# 05_-_Slow_Control.net
KiCad netlist of a schematic drawn in Altium Designer
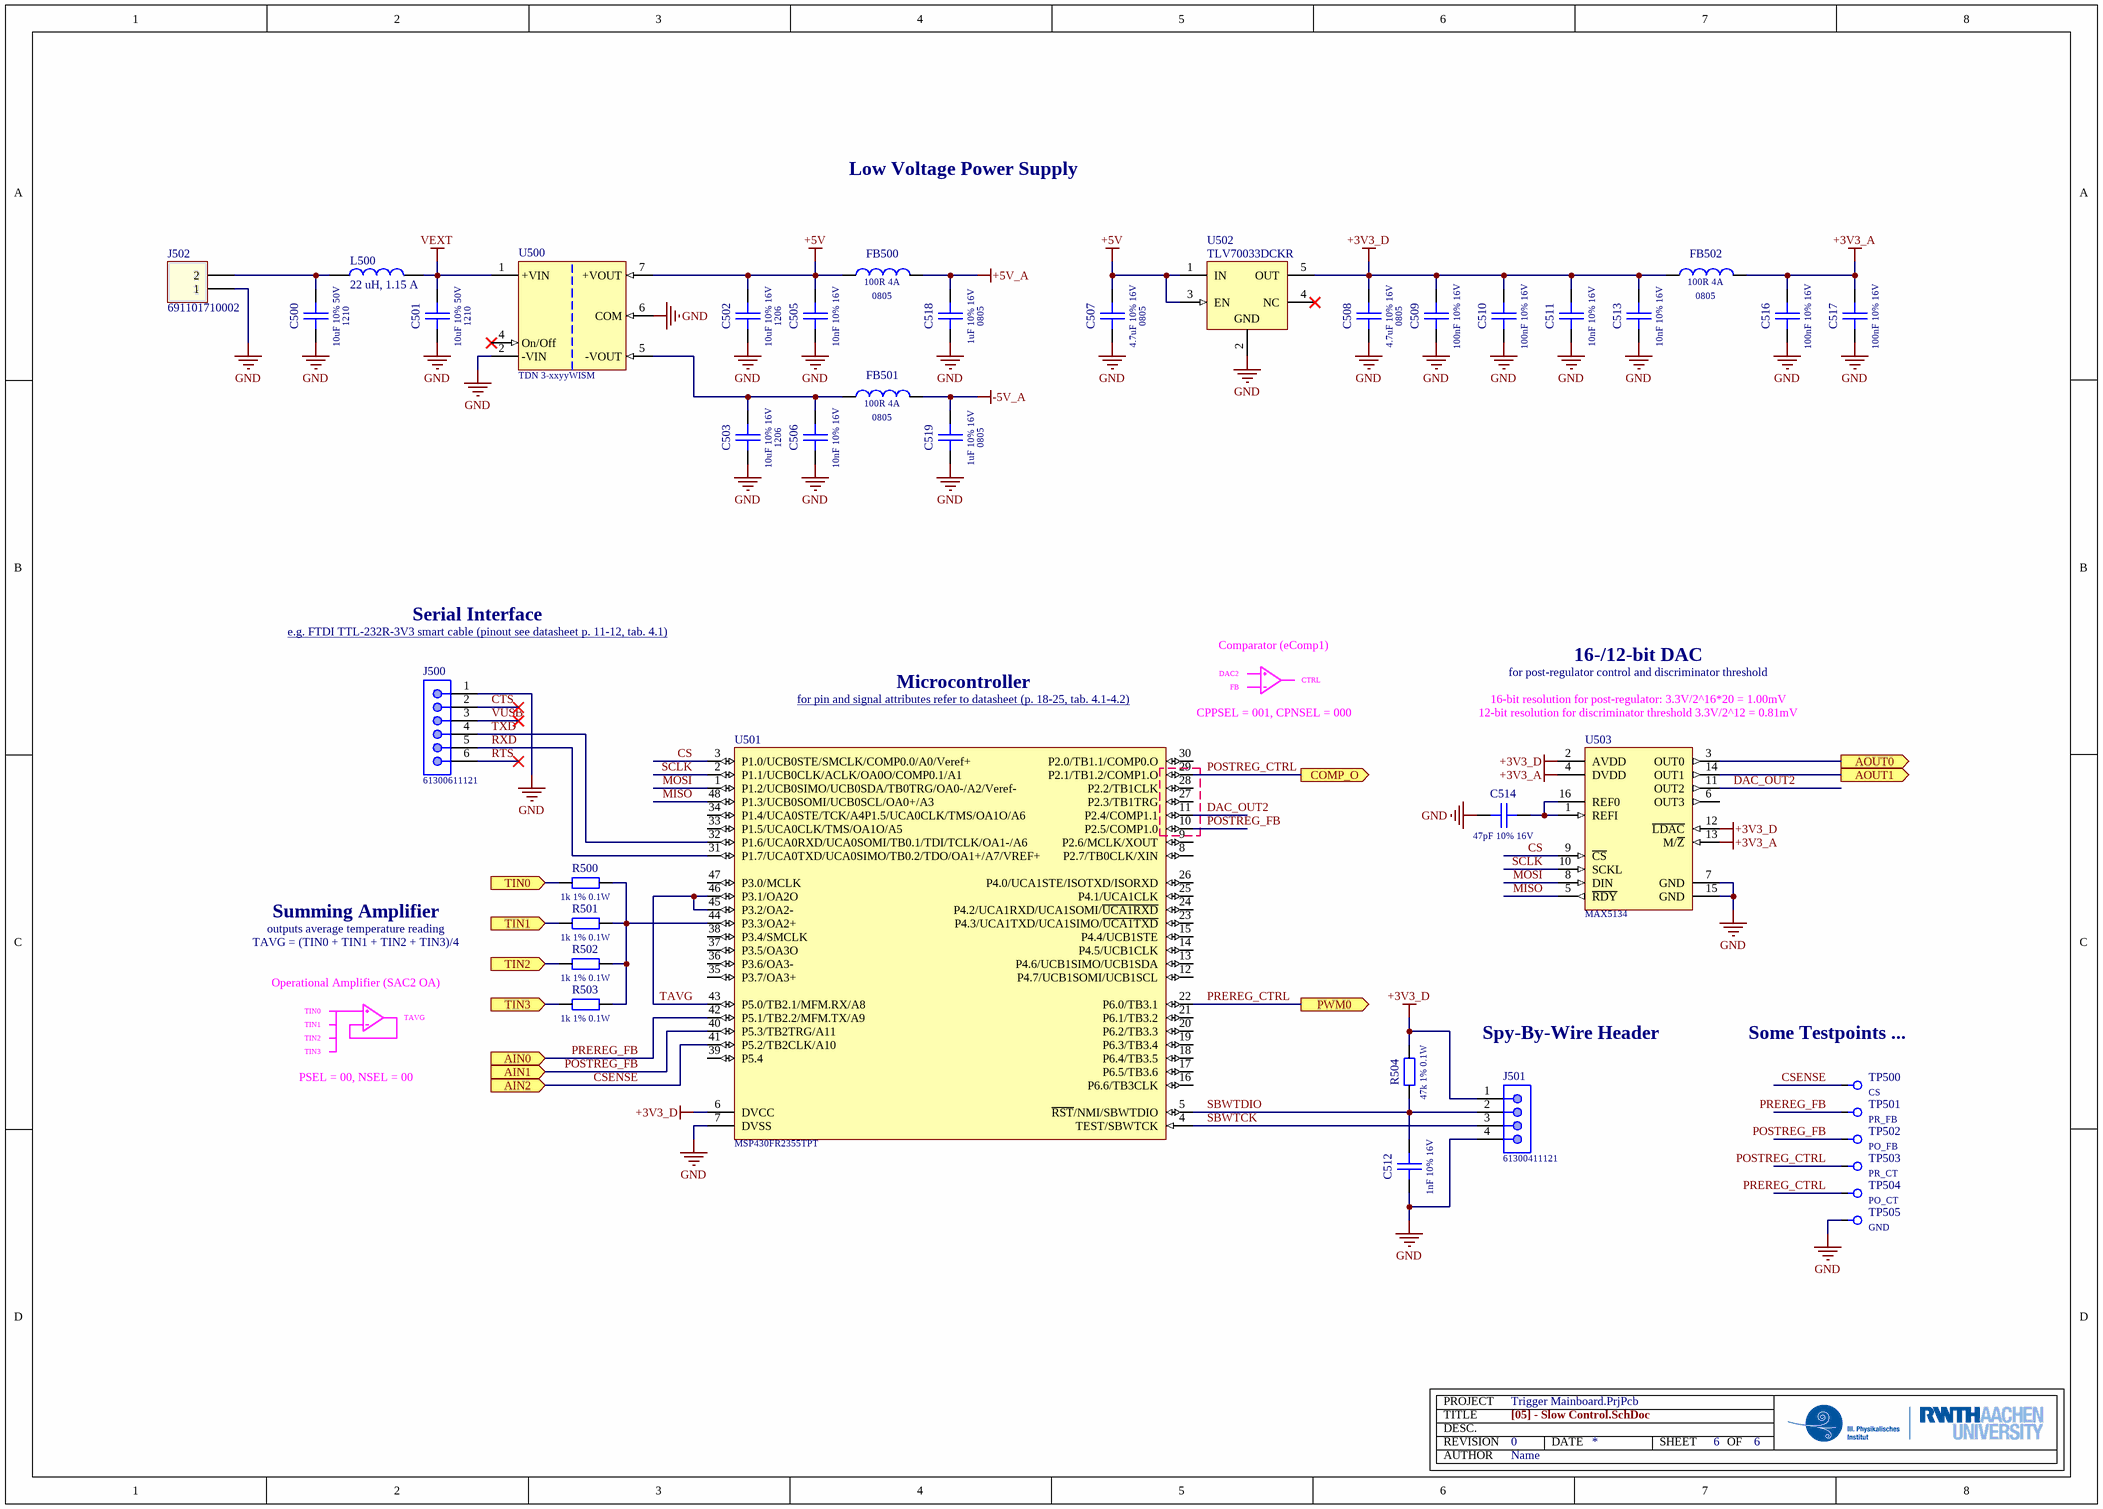
[diagram p0: [05] - Slow Control.SchDoc]

(export (version "E")
  (design (tool "Eeschema 10.0.6"))
  (components
    (comp (ref "C500")
      (value "10uF 10% 50V")
      (footprint "1210_CAP")
      (description "Simple generic capacitor.")
      (fields (field (name "PACKAGEREFERENCE") "1210"))
      (libsource (lib "CustomComponents") (part "Capacitor"))
    )
    (comp (ref "C501")
      (value "10uF 10% 50V")
      (footprint "1210_CAP")
      (description "Simple generic capacitor.")
      (fields (field (name "PACKAGEREFERENCE") "1210"))
      (libsource (lib "CustomComponents") (part "Capacitor"))
    )
    (comp (ref "C502")
      (value "10uF 10% 16V")
      (footprint "1206_CAP")
      (description "Simple generic capacitor.")
      (fields (field (name "PACKAGEREFERENCE") "1206"))
      (libsource (lib "CustomComponents") (part "Capacitor"))
    )
    (comp (ref "C503")
      (value "10uF 10% 16V")
      (footprint "1206_CAP")
      (description "Simple generic capacitor.")
      (fields (field (name "PACKAGEREFERENCE") "1206"))
      (libsource (lib "CustomComponents") (part "Capacitor"))
    )
    (comp (ref "C505")
      (value "10nF 10% 16V")
      (footprint "0603_CAP")
      (description "Simple generic capacitor.")
      (libsource (lib "CustomComponents") (part "Capacitor"))
    )
    (comp (ref "C506")
      (value "10nF 10% 16V")
      (footprint "0603_CAP")
      (description "Simple generic capacitor.")
      (libsource (lib "CustomComponents") (part "Capacitor"))
    )
    (comp (ref "C507")
      (value "4.7uF 10% 16V")
      (footprint "0805_CAP")
      (description "Simple generic capacitor.")
      (fields (field (name "PACKAGEREFERENCE") "0805"))
      (libsource (lib "CustomComponents") (part "Capacitor"))
    )
    (comp (ref "C508")
      (value "4.7uF 10% 16V")
      (footprint "0805_CAP")
      (description "Simple generic capacitor.")
      (fields (field (name "PACKAGEREFERENCE") "0805"))
      (libsource (lib "CustomComponents") (part "Capacitor"))
    )
    (comp (ref "C509")
      (value "100nF 10% 16V")
      (footprint "0603_CAP")
      (description "Simple generic capacitor.")
      (libsource (lib "CustomComponents") (part "Capacitor"))
    )
    (comp (ref "C510")
      (value "100nF 10% 16V")
      (footprint "0603_CAP")
      (description "Simple generic capacitor.")
      (libsource (lib "CustomComponents") (part "Capacitor"))
    )
    (comp (ref "C511")
      (value "10nF 10% 16V")
      (footprint "0603_CAP")
      (description "Simple generic capacitor.")
      (libsource (lib "CustomComponents") (part "Capacitor"))
    )
    (comp (ref "C512")
      (value "1nF 10% 16V")
      (footprint "0603_CAP")
      (description "Simple generic capacitor.")
      (libsource (lib "CustomComponents") (part "Capacitor"))
    )
    (comp (ref "C513")
      (value "10nF 10% 16V")
      (footprint "0603_CAP")
      (description "Simple generic capacitor.")
      (libsource (lib "CustomComponents") (part "Capacitor"))
    )
    (comp (ref "C514")
      (value "47pF 10% 16V")
      (footprint "0603_CAP")
      (description "Simple generic capacitor.")
      (libsource (lib "CustomComponents") (part "Capacitor"))
    )
    (comp (ref "C516")
      (value "100nF 10% 16V")
      (footprint "0603_CAP")
      (description "Simple generic capacitor.")
      (libsource (lib "CustomComponents") (part "Capacitor"))
    )
    (comp (ref "C517")
      (value "100nF 10% 16V")
      (footprint "0603_CAP")
      (description "Simple generic capacitor.")
      (libsource (lib "CustomComponents") (part "Capacitor"))
    )
    (comp (ref "C518")
      (value "1uF 10% 16V")
      (footprint "0805_CAP")
      (description "Simple generic capacitor.")
      (fields (field (name "PACKAGEREFERENCE") "0805"))
      (libsource (lib "CustomComponents") (part "Capacitor"))
    )
    (comp (ref "C519")
      (value "1uF 10% 16V")
      (footprint "0805_CAP")
      (description "Simple generic capacitor.")
      (fields (field (name "PACKAGEREFERENCE") "0805"))
      (libsource (lib "CustomComponents") (part "Capacitor"))
    )
    (comp (ref "FB500")
      (value "100R 4A")
      (footprint "0805_RES")
      (description "Simple generic inductor.")
      (fields
        (field (name "MANUFACTURER") "TDK")
        (field (name "PARTNUMBER") "MPZ2012S101ATD25")
        (field (name "PACKAGEREFERENCE") "0805")
      )
      (libsource (lib "CustomComponents") (part "Inductor"))
    )
    (comp (ref "FB501")
      (value "100R 4A")
      (footprint "0805_RES")
      (description "Simple generic inductor.")
      (fields
        (field (name "MANUFACTURER") "TDK")
        (field (name "PARTNUMBER") "MPZ2012S101ATD25")
        (field (name "PACKAGEREFERENCE") "0805")
      )
      (libsource (lib "CustomComponents") (part "Inductor"))
    )
    (comp (ref "FB502")
      (value "100R 4A")
      (footprint "0603_RES")
      (description "Simple generic inductor.")
      (fields
        (field (name "MANUFACTURER") "TDK")
        (field (name "PARTNUMBER") "MPZ2012S101ATD25")
        (field (name "PACKAGEREFERENCE") "0805")
      )
      (libsource (lib "CustomComponents") (part "Inductor"))
    )
    (comp (ref "J500")
      (value "61300611121")
      (footprint "61300611121")
      (description "WR-PHD Pin Header, THT, pitch 2.54mm, Single Row, Vertical, 6pin")
      (fields (field (name "PUBLISHER") "Wurth Elektronik"))
      (libsource (lib "WR-PHD") (part "61300611121"))
    )
    (comp (ref "J501")
      (value "61300411121")
      (footprint "61300411121")
      (description "WR-PHD Pin Header, THT, pitch 2.54mm, Single Row, Vertical, 4pin")
      (fields (field (name "PUBLISHER") "Wurth Elektronik"))
      (libsource (lib "WR-PHD") (part "61300411121"))
    )
    (comp (ref "J502")
      (value "691101710002")
      (footprint "691101710002")
      (description "WR-TBL Serie 101 - 5.00 mm Horizontal Entry Modular, 02p")
      (fields (field (name "PUBLISHER") "Wurth Elektronik"))
      (libsource (lib "WE-5.00mm Header") (part "691101710002"))
    )
    (comp (ref "L500")
      (value "22 uH, 1.15 A")
      (footprint "WE-TPC_5828")
      (description "SMT Shielded Tiny Power Inductor WE-TPC, size 5828, 22 uH, 1.15 A")
      (fields (field (name "PART NUMBER") "744053220") (field (name "PUBLISHER") "Wurth Elektronik"))
      (libsource (lib "altium-import") (part "root_0_744053220_"))
    )
    (comp (ref "R500")
      (value "1k 1% 0.1W")
      (footprint "0603_RES")
      (description "Simple generic resistor.")
      (libsource (lib "CustomComponents") (part "Resistor"))
    )
    (comp (ref "R501")
      (value "1k 1% 0.1W")
      (footprint "0603_RES")
      (description "Simple generic resistor.")
      (libsource (lib "CustomComponents") (part "Resistor"))
    )
    (comp (ref "R502")
      (value "1k 1% 0.1W")
      (footprint "0603_RES")
      (description "Simple generic resistor.")
      (libsource (lib "CustomComponents") (part "Resistor"))
    )
    (comp (ref "R503")
      (value "1k 1% 0.1W")
      (footprint "0603_RES")
      (description "Simple generic resistor.")
      (libsource (lib "CustomComponents") (part "Resistor"))
    )
    (comp (ref "R504")
      (value "47k 1% 0.1W")
      (footprint "0603_RES")
      (description "Simple generic resistor.")
      (libsource (lib "CustomComponents") (part "Resistor"))
    )
    (comp (ref "TP500")
      (value "CS")
      (footprint "TESTPOINT_5019")
      (fields (field (name "MANUFACTURER") "Keystone Electronics") (field (name "PARTNUMBER") "500X"))
      (libsource (lib "CustomComponents") (part "Testpoint"))
    )
    (comp (ref "TP501")
      (value "PR_FB")
      (footprint "TESTPOINT_5019")
      (fields (field (name "MANUFACTURER") "Keystone Electronics") (field (name "PARTNUMBER") "500X"))
      (libsource (lib "CustomComponents") (part "Testpoint"))
    )
    (comp (ref "TP502")
      (value "PO_FB")
      (footprint "TESTPOINT_5019")
      (fields (field (name "MANUFACTURER") "Keystone Electronics") (field (name "PARTNUMBER") "500X"))
      (libsource (lib "CustomComponents") (part "Testpoint"))
    )
    (comp (ref "TP503")
      (value "PR_CT")
      (footprint "TESTPOINT_5019")
      (fields (field (name "MANUFACTURER") "Keystone Electronics") (field (name "PARTNUMBER") "500X"))
      (libsource (lib "CustomComponents") (part "Testpoint"))
    )
    (comp (ref "TP504")
      (value "PO_CT")
      (footprint "TESTPOINT_5019")
      (fields (field (name "MANUFACTURER") "Keystone Electronics") (field (name "PARTNUMBER") "500X"))
      (libsource (lib "CustomComponents") (part "Testpoint"))
    )
    (comp (ref "TP505")
      (value "GND")
      (footprint "TESTPOINT_5019")
      (fields (field (name "MANUFACTURER") "Keystone Electronics") (field (name "PARTNUMBER") "500X"))
      (libsource (lib "CustomComponents") (part "Testpoint"))
    )
    (comp (ref "U500")
      (value "TDN 3-xxyyWISM")
      (footprint "TDN_3WISM-PACK")
      (description "TDN 3WISM Series, 3 Watt DC/DC converter.")
      (fields (field (name "MANUFACTURER") "Traco Power"))
      (libsource (lib "CustomComponents") (part "_BLANK_1"))
    )
    (comp (ref "U501")
      (value "MSP430FR2355TPT")
      (footprint "PQFP-48")
      (description "Mixed-Signal Microcontroller.")
      (fields (field (name "MANUFACTURER") "Texas Instruments"))
      (libsource (lib "CustomComponents") (part "MSP430FR2355TPT"))
    )
    (comp (ref "U502")
      (value "TLV70033DCKR")
      (footprint "TI-DCK5_V")
      (fields (field (name "MANUFACTURER") "Texas Instruments"))
      (libsource (lib "TI Power Management Linear Regulator Single Channel LDO (0-350mA)") (part "TLV70033DCKR"))
    )
    (comp (ref "U503")
      (value "MAX5134")
      (footprint "TSSOP-16")
      (description "Pin-/Software-Compatible, 16-/12-Bit, Voltage-Output DACs.")
      (fields (field (name "MANUFACTURER") "Maxim Integrated") (field (name "PARTNUMBER") "MAX5134AGUE+"))
      (libsource (lib "CustomComponents") (part "MAX5134"))
    )
  )
  (nets
    (net (code "1") (name "+3V3_A") (class "Default")
      (node (ref "C516") (pin "2") (pinfunction "2_2") (pintype "passive"))
      (node (ref "C517") (pin "2") (pinfunction "2_2") (pintype "passive"))
      (node (ref "FB502") (pin "2") (pinfunction "2_2") (pintype "passive"))
      (node (ref "U503") (pin "13") (pinfunction "M/~{Z}_13") (pintype "input"))
      (node (ref "U503") (pin "4") (pinfunction "DVDD_4") (pintype "power_in"))
    )
    (net (code "2") (name "+3V3_D") (class "Default")
      (node (ref "C508") (pin "2") (pinfunction "2_2") (pintype "passive"))
      (node (ref "C509") (pin "2") (pinfunction "2_2") (pintype "passive"))
      (node (ref "C510") (pin "2") (pinfunction "2_2") (pintype "passive"))
      (node (ref "C511") (pin "2") (pinfunction "2_2") (pintype "passive"))
      (node (ref "C513") (pin "2") (pinfunction "2_2") (pintype "passive"))
      (node (ref "FB502") (pin "1") (pinfunction "1_1") (pintype "passive"))
      (node (ref "J501") (pin "1") (pinfunction "1_1") (pintype "passive"))
      (node (ref "R504") (pin "1") (pinfunction "1_1") (pintype "passive"))
      (node (ref "U501") (pin "6") (pinfunction "DVCC_6") (pintype "passive"))
      (node (ref "U502") (pin "5") (pinfunction "OUT_5") (pintype "power_in"))
      (node (ref "U503") (pin "12") (pinfunction "~{LDAC}_12") (pintype "input"))
      (node (ref "U503") (pin "2") (pinfunction "AVDD_2") (pintype "power_in"))
    )
    (net (code "3") (name "+5V") (class "Default")
      (node (ref "C502") (pin "2") (pinfunction "2_2") (pintype "passive"))
      (node (ref "C505") (pin "2") (pinfunction "2_2") (pintype "passive"))
      (node (ref "C507") (pin "2") (pinfunction "2_2") (pintype "passive"))
      (node (ref "FB500") (pin "1") (pinfunction "1_1") (pintype "passive"))
      (node (ref "U500") (pin "7") (pinfunction "+VOUT_7") (pintype "input"))
      (node (ref "U502") (pin "1") (pinfunction "IN_1") (pintype "power_in"))
      (node (ref "U502") (pin "3") (pinfunction "EN_3") (pintype "input"))
    )
    (net (code "4") (name "+5V_A") (class "Default")
      (node (ref "C518") (pin "2") (pinfunction "2_2") (pintype "passive"))
      (node (ref "FB500") (pin "2") (pinfunction "2_2") (pintype "passive"))
    )
    (net (code "5") (name "-5V_A") (class "Default")
      (node (ref "C519") (pin "2") (pinfunction "2_2") (pintype "passive"))
      (node (ref "FB501") (pin "2") (pinfunction "2_2") (pintype "passive"))
    )
    (net (code "6") (name "/AOUT0") (class "Default")
      (node (ref "U503") (pin "3") (pinfunction "OUT0_3") (pintype "output"))
    )
    (net (code "7") (name "/AOUT1") (class "Default")
      (node (ref "U503") (pin "14") (pinfunction "OUT1_14") (pintype "output"))
    )
    (net (code "8") (name "/CS") (class "Default")
      (node (ref "U501") (pin "3") (pinfunction "P1.0/UCB0STE/SMCLK/COMP0.0/A0/Veref+_3") (pintype "bidirectional"))
      (node (ref "U503") (pin "9") (pinfunction "~{CS}_9") (pintype "input"))
    )
    (net (code "9") (name "/CSENSE") (class "Default")
      (node (ref "TP500") (pin "1") (pinfunction "1_1") (pintype "passive"))
      (node (ref "U501") (pin "41") (pinfunction "P5.2/TB2CLK/A10_41") (pintype "bidirectional"))
    )
    (net (code "10") (name "/DAC_OUT2") (class "Default")
      (node (ref "U501") (pin "11") (pinfunction "P2.4/COMP1.1_11") (pintype "bidirectional"))
      (node (ref "U503") (pin "11") (pinfunction "OUT2_11") (pintype "output"))
    )
    (net (code "11") (name "/MISO") (class "Default")
      (node (ref "U501") (pin "48") (pinfunction "P1.3/UCB0SOMI/UCB0SCL/OA0+/A3_48") (pintype "bidirectional"))
      (node (ref "U503") (pin "5") (pinfunction "~{RDY}_5") (pintype "output"))
    )
    (net (code "12") (name "/MOSI") (class "Default")
      (node (ref "U501") (pin "1") (pinfunction "P1.2/UCB0SIMO/UCB0SDA/TB0TRG/OA0-/A2/Veref-_1") (pintype "bidirectional"))
      (node (ref "U503") (pin "8") (pinfunction "DIN_8") (pintype "input"))
    )
    (net (code "13") (name "/POSTREG_CTRL") (class "Default")
      (node (ref "TP503") (pin "1") (pinfunction "1_1") (pintype "passive"))
      (node (ref "U501") (pin "29") (pinfunction "P2.1/TB1.2/COMP1.O_29") (pintype "bidirectional"))
    )
    (net (code "14") (name "/POSTREG_FB") (class "Default")
      (node (ref "TP502") (pin "1") (pinfunction "1_1") (pintype "passive"))
      (node (ref "U501") (pin "10") (pinfunction "P2.5/COMP1.0_10") (pintype "bidirectional"))
      (node (ref "U501") (pin "40") (pinfunction "P5.3/TB2TRG/A11_40") (pintype "bidirectional"))
    )
    (net (code "15") (name "/PREREG_CTRL") (class "Default")
      (node (ref "TP504") (pin "1") (pinfunction "1_1") (pintype "passive"))
      (node (ref "U501") (pin "22") (pinfunction "P6.0/TB3.1_22") (pintype "bidirectional"))
    )
    (net (code "16") (name "/PREREG_FB") (class "Default")
      (node (ref "TP501") (pin "1") (pinfunction "1_1") (pintype "passive"))
      (node (ref "U501") (pin "42") (pinfunction "P5.1/TB2.2/MFM.TX/A9_42") (pintype "bidirectional"))
    )
    (net (code "17") (name "/RXD") (class "Default")
      (node (ref "J500") (pin "5") (pinfunction "5_5") (pintype "passive"))
      (node (ref "U501") (pin "31") (pinfunction "P1.7/UCA0TXD/UCA0SIMO/TB0.2/TDO/OA1+/A7/VREF+_31") (pintype "bidirectional"))
    )
    (net (code "18") (name "/SBWTCK") (class "Default")
      (node (ref "J501") (pin "3") (pinfunction "3_3") (pintype "passive"))
      (node (ref "U501") (pin "4") (pinfunction "TEST/SBWTCK_4") (pintype "input"))
    )
    (net (code "19") (name "/SBWTDIO") (class "Default")
      (node (ref "C512") (pin "2") (pinfunction "2_2") (pintype "passive"))
      (node (ref "J501") (pin "2") (pinfunction "2_2") (pintype "passive"))
      (node (ref "R504") (pin "2") (pinfunction "2_2") (pintype "passive"))
      (node (ref "U501") (pin "5") (pinfunction "~{RST}/NMI/SBWTDIO_5") (pintype "bidirectional"))
    )
    (net (code "20") (name "/SCLK") (class "Default")
      (node (ref "U501") (pin "2") (pinfunction "P1.1/UCB0CLK/ACLK/OA0O/COMP0.1/A1_2") (pintype "bidirectional"))
      (node (ref "U503") (pin "10") (pinfunction "SCKL_10") (pintype "input"))
    )
    (net (code "21") (name "/TAVG") (class "Default")
      (node (ref "U501") (pin "43") (pinfunction "P5.0/TB2.1/MFM.RX/A8_43") (pintype "bidirectional"))
      (node (ref "U501") (pin "45") (pinfunction "P3.2/OA2-_45") (pintype "bidirectional"))
      (node (ref "U501") (pin "46") (pinfunction "P3.1/OA2O_46") (pintype "bidirectional"))
    )
    (net (code "22") (name "/TIN0") (class "Default")
      (node (ref "R500") (pin "2") (pinfunction "2_2") (pintype "passive"))
    )
    (net (code "23") (name "/TIN1") (class "Default")
      (node (ref "R501") (pin "2") (pinfunction "2_2") (pintype "passive"))
    )
    (net (code "24") (name "/TIN2") (class "Default")
      (node (ref "R502") (pin "2") (pinfunction "2_2") (pintype "passive"))
    )
    (net (code "25") (name "/TIN3") (class "Default")
      (node (ref "R503") (pin "2") (pinfunction "2_2") (pintype "passive"))
    )
    (net (code "26") (name "/TXD") (class "Default")
      (node (ref "J500") (pin "4") (pinfunction "4_4") (pintype "passive"))
      (node (ref "U501") (pin "32") (pinfunction "P1.6/UCA0RXD/UCA0SOMI/TB0.1/TDI/TCLK/OA1-/A6_32") (pintype "bidirectional"))
    )
    (net (code "27") (name "/VUSB") (class "Default")
      (node (ref "J500") (pin "3") (pinfunction "3_3") (pintype "passive+no_connect"))
    )
    (net (code "28") (name "/~{CTS}") (class "Default")
      (node (ref "J500") (pin "2") (pinfunction "2_2") (pintype "passive+no_connect"))
    )
    (net (code "29") (name "/~{RTS}") (class "Default")
      (node (ref "J500") (pin "6") (pinfunction "6_6") (pintype "passive+no_connect"))
    )
    (net (code "30") (name "GND") (class "Default")
      (node (ref "C500") (pin "1") (pinfunction "1_1") (pintype "passive"))
      (node (ref "C501") (pin "1") (pinfunction "1_1") (pintype "passive"))
      (node (ref "C502") (pin "1") (pinfunction "1_1") (pintype "passive"))
      (node (ref "C503") (pin "1") (pinfunction "1_1") (pintype "passive"))
      (node (ref "C505") (pin "1") (pinfunction "1_1") (pintype "passive"))
      (node (ref "C506") (pin "1") (pinfunction "1_1") (pintype "passive"))
      (node (ref "C507") (pin "1") (pinfunction "1_1") (pintype "passive"))
      (node (ref "C508") (pin "1") (pinfunction "1_1") (pintype "passive"))
      (node (ref "C509") (pin "1") (pinfunction "1_1") (pintype "passive"))
      (node (ref "C510") (pin "1") (pinfunction "1_1") (pintype "passive"))
      (node (ref "C511") (pin "1") (pinfunction "1_1") (pintype "passive"))
      (node (ref "C512") (pin "1") (pinfunction "1_1") (pintype "passive"))
      (node (ref "C513") (pin "1") (pinfunction "1_1") (pintype "passive"))
      (node (ref "C514") (pin "1") (pinfunction "1_1") (pintype "passive"))
      (node (ref "C516") (pin "1") (pinfunction "1_1") (pintype "passive"))
      (node (ref "C517") (pin "1") (pinfunction "1_1") (pintype "passive"))
      (node (ref "C518") (pin "1") (pinfunction "1_1") (pintype "passive"))
      (node (ref "C519") (pin "1") (pinfunction "1_1") (pintype "passive"))
      (node (ref "J500") (pin "1") (pinfunction "1_1") (pintype "passive"))
      (node (ref "J501") (pin "4") (pinfunction "4_4") (pintype "passive"))
      (node (ref "J502") (pin "1") (pinfunction "1_1") (pintype "passive"))
      (node (ref "TP505") (pin "1") (pinfunction "1_1") (pintype "passive"))
      (node (ref "U500") (pin "2") (pinfunction "-VIN_2") (pintype "power_in"))
      (node (ref "U500") (pin "6") (pinfunction "COM_6") (pintype "input"))
      (node (ref "U501") (pin "7") (pinfunction "DVSS_7") (pintype "passive"))
      (node (ref "U502") (pin "2") (pinfunction "GND_2") (pintype "power_in"))
      (node (ref "U503") (pin "15") (pinfunction "GND_15") (pintype "power_in"))
      (node (ref "U503") (pin "7") (pinfunction "GND_7") (pintype "power_in"))
    )
    (net (code "31") (name "Net-(C500-Pad2)") (class "Default")
      (node (ref "C500") (pin "2") (pinfunction "2_2") (pintype "passive"))
      (node (ref "J502") (pin "2") (pinfunction "2_2") (pintype "passive"))
      (node (ref "L500") (pin "1") (pinfunction "1_1") (pintype "passive"))
    )
    (net (code "32") (name "Net-(U500--VOUT)") (class "Default")
      (node (ref "C503") (pin "2") (pinfunction "2_2") (pintype "passive"))
      (node (ref "C506") (pin "2") (pinfunction "2_2") (pintype "passive"))
      (node (ref "FB501") (pin "1") (pinfunction "1_1") (pintype "passive"))
      (node (ref "U500") (pin "5") (pinfunction "-VOUT_5") (pintype "input"))
    )
    (net (code "33") (name "Net-(U501-P3.3{slash}OA2+)") (class "Default")
      (node (ref "R500") (pin "1") (pinfunction "1_1") (pintype "passive"))
      (node (ref "R501") (pin "1") (pinfunction "1_1") (pintype "passive"))
      (node (ref "R502") (pin "1") (pinfunction "1_1") (pintype "passive"))
      (node (ref "R503") (pin "1") (pinfunction "1_1") (pintype "passive"))
      (node (ref "U501") (pin "44") (pinfunction "P3.3/OA2+_44") (pintype "bidirectional"))
    )
    (net (code "34") (name "Net-(U503-REF0)") (class "Default")
      (node (ref "C514") (pin "2") (pinfunction "2_2") (pintype "passive"))
      (node (ref "U503") (pin "1") (pinfunction "REFI_1") (pintype "input"))
      (node (ref "U503") (pin "16") (pinfunction "REF0_16") (pintype "power_in"))
    )
    (net (code "35") (name "VEXT") (class "Default")
      (node (ref "C501") (pin "2") (pinfunction "2_2") (pintype "passive"))
      (node (ref "L500") (pin "2") (pinfunction "2_2") (pintype "passive"))
      (node (ref "U500") (pin "1") (pinfunction "+VIN_1") (pintype "power_in"))
    )
    (net (code "36") (name "unconnected-(U500-On{slash}Off-Pad4)") (class "Default")
      (node (ref "U500") (pin "4") (pinfunction "On/Off_4") (pintype "input+no_connect"))
    )
    (net (code "37") (name "unconnected-(U501-P1.4{slash}UCA0STE{slash}TCK{slash}A4P1.5{slash}UCA0CLK{slash}TMS{slash}OA1O{slash}A6-Pad34)") (class "Default")
      (node (ref "U501") (pin "34") (pinfunction "P1.4/UCA0STE/TCK/A4P1.5/UCA0CLK/TMS/OA1O/A6_34") (pintype "bidirectional"))
    )
    (net (code "38") (name "unconnected-(U501-P1.5{slash}UCA0CLK{slash}TMS{slash}OA1O{slash}A5-Pad33)") (class "Default")
      (node (ref "U501") (pin "33") (pinfunction "P1.5/UCA0CLK/TMS/OA1O/A5_33") (pintype "bidirectional"))
    )
    (net (code "39") (name "unconnected-(U501-P2.0{slash}TB1.1{slash}COMP0.O-Pad30)") (class "Default")
      (node (ref "U501") (pin "30") (pinfunction "P2.0/TB1.1/COMP0.O_30") (pintype "bidirectional"))
    )
    (net (code "40") (name "unconnected-(U501-P2.2{slash}TB1CLK-Pad28)") (class "Default")
      (node (ref "U501") (pin "28") (pinfunction "P2.2/TB1CLK_28") (pintype "bidirectional"))
    )
    (net (code "41") (name "unconnected-(U501-P2.3{slash}TB1TRG-Pad27)") (class "Default")
      (node (ref "U501") (pin "27") (pinfunction "P2.3/TB1TRG_27") (pintype "bidirectional"))
    )
    (net (code "42") (name "unconnected-(U501-P2.6{slash}MCLK{slash}XOUT-Pad9)") (class "Default")
      (node (ref "U501") (pin "9") (pinfunction "P2.6/MCLK/XOUT_9") (pintype "bidirectional"))
    )
    (net (code "43") (name "unconnected-(U501-P2.7{slash}TB0CLK{slash}XIN-Pad8)") (class "Default")
      (node (ref "U501") (pin "8") (pinfunction "P2.7/TB0CLK/XIN_8") (pintype "bidirectional"))
    )
    (net (code "44") (name "unconnected-(U501-P3.0{slash}MCLK-Pad47)") (class "Default")
      (node (ref "U501") (pin "47") (pinfunction "P3.0/MCLK_47") (pintype "bidirectional"))
    )
    (net (code "45") (name "unconnected-(U501-P3.4{slash}SMCLK-Pad38)") (class "Default")
      (node (ref "U501") (pin "38") (pinfunction "P3.4/SMCLK_38") (pintype "bidirectional"))
    )
    (net (code "46") (name "unconnected-(U501-P3.5{slash}OA3O-Pad37)") (class "Default")
      (node (ref "U501") (pin "37") (pinfunction "P3.5/OA3O_37") (pintype "bidirectional"))
    )
    (net (code "47") (name "unconnected-(U501-P3.6{slash}OA3--Pad36)") (class "Default")
      (node (ref "U501") (pin "36") (pinfunction "P3.6/OA3-_36") (pintype "bidirectional"))
    )
    (net (code "48") (name "unconnected-(U501-P3.7{slash}OA3+-Pad35)") (class "Default")
      (node (ref "U501") (pin "35") (pinfunction "P3.7/OA3+_35") (pintype "bidirectional"))
    )
    (net (code "49") (name "unconnected-(U501-P4.0{slash}UCA1STE{slash}ISOTXD{slash}ISORXD-Pad26)") (class "Default")
      (node (ref "U501") (pin "26") (pinfunction "P4.0/UCA1STE/ISOTXD/ISORXD_26") (pintype "bidirectional"))
    )
    (net (code "50") (name "unconnected-(U501-P4.1{slash}UCA1CLK-Pad25)") (class "Default")
      (node (ref "U501") (pin "25") (pinfunction "P4.1/UCA1CLK_25") (pintype "bidirectional"))
    )
    (net (code "51") (name "unconnected-(U501-P4.2{slash}UCA1RXD{slash}UCA1SOMI{slash}~{UCA1RXD}-Pad24)") (class "Default")
      (node (ref "U501") (pin "24") (pinfunction "P4.2/UCA1RXD/UCA1SOMI/~{UCA1RXD}_24") (pintype "bidirectional"))
    )
    (net (code "52") (name "unconnected-(U501-P4.3{slash}UCA1TXD{slash}UCA1SIMO{slash}~{UCA1TXD}-Pad23)") (class "Default")
      (node (ref "U501") (pin "23") (pinfunction "P4.3/UCA1TXD/UCA1SIMO/~{UCA1TXD}_23") (pintype "bidirectional"))
    )
    (net (code "53") (name "unconnected-(U501-P4.4{slash}UCB1STE-Pad15)") (class "Default")
      (node (ref "U501") (pin "15") (pinfunction "P4.4/UCB1STE_15") (pintype "bidirectional"))
    )
    (net (code "54") (name "unconnected-(U501-P4.5{slash}UCB1CLK-Pad14)") (class "Default")
      (node (ref "U501") (pin "14") (pinfunction "P4.5/UCB1CLK_14") (pintype "bidirectional"))
    )
    (net (code "55") (name "unconnected-(U501-P4.6{slash}UCB1SIMO{slash}UCB1SDA-Pad13)") (class "Default")
      (node (ref "U501") (pin "13") (pinfunction "P4.6/UCB1SIMO/UCB1SDA_13") (pintype "bidirectional"))
    )
    (net (code "56") (name "unconnected-(U501-P4.7{slash}UCB1SOMI{slash}UCB1SCL-Pad12)") (class "Default")
      (node (ref "U501") (pin "12") (pinfunction "P4.7/UCB1SOMI/UCB1SCL_12") (pintype "bidirectional"))
    )
    (net (code "57") (name "unconnected-(U501-P5.4-Pad39)") (class "Default")
      (node (ref "U501") (pin "39") (pinfunction "P5.4_39") (pintype "bidirectional"))
    )
    (net (code "58") (name "unconnected-(U501-P6.1{slash}TB3.2-Pad21)") (class "Default")
      (node (ref "U501") (pin "21") (pinfunction "P6.1/TB3.2_21") (pintype "bidirectional"))
    )
    (net (code "59") (name "unconnected-(U501-P6.2{slash}TB3.3-Pad20)") (class "Default")
      (node (ref "U501") (pin "20") (pinfunction "P6.2/TB3.3_20") (pintype "bidirectional"))
    )
    (net (code "60") (name "unconnected-(U501-P6.3{slash}TB3.4-Pad19)") (class "Default")
      (node (ref "U501") (pin "19") (pinfunction "P6.3/TB3.4_19") (pintype "bidirectional"))
    )
    (net (code "61") (name "unconnected-(U501-P6.4{slash}TB3.5-Pad18)") (class "Default")
      (node (ref "U501") (pin "18") (pinfunction "P6.4/TB3.5_18") (pintype "bidirectional"))
    )
    (net (code "62") (name "unconnected-(U501-P6.5{slash}TB3.6-Pad17)") (class "Default")
      (node (ref "U501") (pin "17") (pinfunction "P6.5/TB3.6_17") (pintype "bidirectional"))
    )
    (net (code "63") (name "unconnected-(U501-P6.6{slash}TB3CLK-Pad16)") (class "Default")
      (node (ref "U501") (pin "16") (pinfunction "P6.6/TB3CLK_16") (pintype "bidirectional"))
    )
    (net (code "64") (name "unconnected-(U502-NC-Pad4)") (class "Default")
      (node (ref "U502") (pin "4") (pinfunction "NC_4") (pintype "passive+no_connect"))
    )
    (net (code "65") (name "unconnected-(U503-OUT3-Pad6)") (class "Default")
      (node (ref "U503") (pin "6") (pinfunction "OUT3_6") (pintype "output"))
    )
  )
)
